# MEMS_Motion_Sensor.net
KiCad netlist of a schematic drawn in Altium Designer
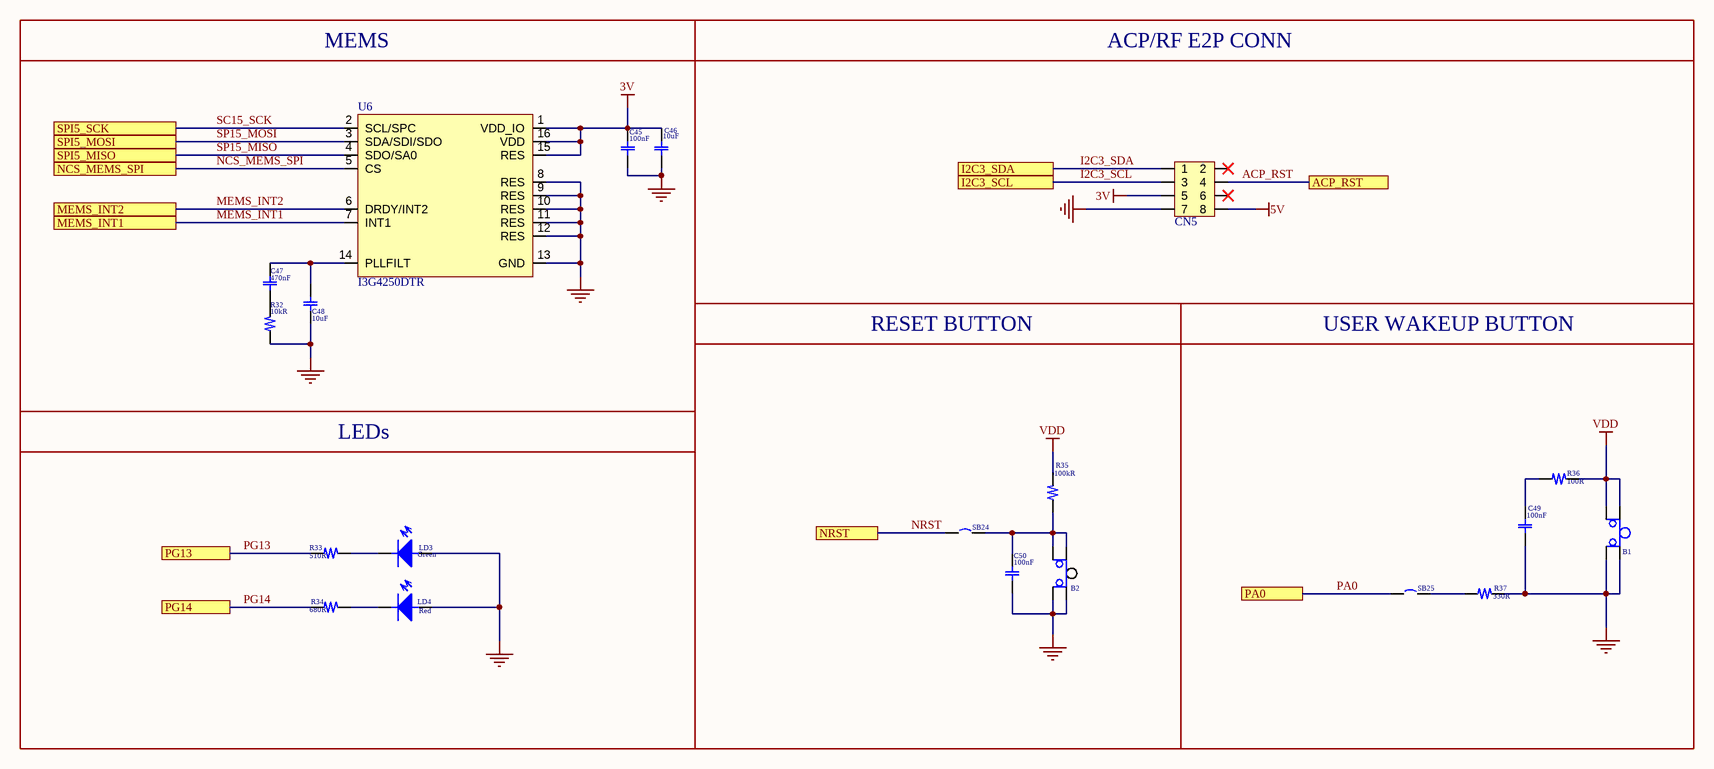
[diagram p0: MEMS Motion Sensor.SchDoc]

(export (version "E")
  (design (tool "Eeschema 10.0.6"))
  (components
    (comp (ref "B1")
      (value "KSC721G LFS")
      (footprint "Blue_Button")
      (description "Switch Tactile N.O. SPST Round Button Gull Wing 0.05A 32VDC 1VA 300000Cycle 1.7N SMD T/R")
      (fields (field (name "MANUFACTURER") "ITT C&K") (field (name "MANUFACTURER PART NUMBER") "KSC721GLFS"))
      (libsource (lib "STM32") (part "BLUE SWITCH TACTILE"))
    )
    (comp (ref "B2")
      (value "KSC321GLFS")
      (footprint "Black_Buttom")
      (fields (field (name "MANUFACTURER") "ITT C&K"))
      (libsource (lib "STM32") (part "BLACK SWITCH TACTILE"))
    )
    (comp (ref "C45")
      (value "100nF")
      (footprint "CAP-0402")
      (description "Multilayer Ceramic Capacitor, 0.1 uF, 25 V, ± 10%, X7R, 0402 [1005 Metric]")
      (fields
        (field (name "MANUFACTURER") "Yageo")
        (field (name "MANUFACTURER PART NUMBER") "CC0402KRX7R7BB104")
      )
      (libsource (lib "STM32") (part "CAP CER 100nF 16V X7R 0402"))
    )
    (comp (ref "C46")
      (value "10uF")
      (footprint "CAP-0603")
      (description "Multilayer Ceramic Capacitor, 10 uF, 10 V, ± 10%, X5R, 0603 [1608 Metric]")
      (fields
        (field (name "MANUFACTURER") "Samsung")
        (field (name "MANUFACTURER PART NUMBER") "CL10A106KP8NNNC")
      )
      (libsource (lib "STM32") (part "CAP CER 10UF 10V X5R 0603"))
    )
    (comp (ref "C47")
      (value "470nF")
      (footprint "CAP-0603")
      (description "Multilayer Ceramic Capacitor, 0.47 uF, 16 V, ± 10%, X7R, 0603 [1608 Metric]")
      (fields
        (field (name "MANUFACTURER") "Yageo")
        (field (name "MANUFACTURER PART NUMBER") "CC0603KRX7R7BB474")
      )
      (libsource (lib "STM32") (part "CAP CER 470nF 16V X7R 0603"))
    )
    (comp (ref "C48")
      (value "10uF")
      (footprint "CAP-0603")
      (description "Multilayer Ceramic Capacitor, 10 uF, 10 V, ± 10%, X5R, 0603 [1608 Metric]")
      (fields
        (field (name "MANUFACTURER") "Samsung")
        (field (name "MANUFACTURER PART NUMBER") "CL10A106KP8NNNC")
      )
      (libsource (lib "STM32") (part "CAP CER 10UF 10V X5R 0603"))
    )
    (comp (ref "C49")
      (value "100nF")
      (footprint "CAP-0402")
      (description "Multilayer Ceramic Capacitor, 0.1 uF, 25 V, ± 10%, X7R, 0402 [1005 Metric]")
      (fields
        (field (name "MANUFACTURER") "Yageo")
        (field (name "MANUFACTURER PART NUMBER") "CC0402KRX7R7BB104")
      )
      (libsource (lib "STM32") (part "CAP CER 100nF 16V X7R 0402"))
    )
    (comp (ref "C50")
      (value "100nF")
      (footprint "CAP-0402")
      (description "Multilayer Ceramic Capacitor, 0.1 uF, 25 V, ± 10%, X7R, 0402 [1005 Metric]")
      (fields
        (field (name "MANUFACTURER") "Yageo")
        (field (name "MANUFACTURER PART NUMBER") "CC0402KRX7R7BB104")
      )
      (libsource (lib "STM32") (part "CAP CER 100nF 16V X7R 0402"))
    )
    (comp (ref "CN5")
      (value "SSM-104-L-DH")
      (footprint "CONN-2*8")
      (description "Connector Socket Strip SKT 8 POS 2.54mm Solder RA SMD")
      (fields (field (name "MANUFACTURER") "Samtec"))
      (libsource (lib "STM32") (part "CONN 2*8POS 2.54MM"))
    )
    (comp (ref "LD3")
      (value "150060VS75000")
      (footprint "LED-GREEN-0603")
      (description "WURTH ELEKTRONIK - 150060VS75000 - LED, Green, SMD, 0603, 30 mA, 2 V, 570 nm")
      (fields (field (name "MANUFACTURER") "Wurth Electronics") (field (name "COLOR") "Green"))
      (libsource (lib "STM32") (part "LED GREEN CLEAR 0603 SMD"))
    )
    (comp (ref "LD4")
      (value "150060RS75000")
      (footprint "LED-RED-0603")
      (description "LED Low-Power Uni-Color Red 630nm 2V 2-Pin Chip 0603(1608Metric) T/R")
      (fields (field (name "MANUFACTURER") "Wurth Electronics") (field (name "COLOR") "Red"))
      (libsource (lib "STM32") (part "LED RED CLEAR 0603 SMD"))
    )
    (comp (ref "R32")
      (value "10kR")
      (footprint "RES-0402")
      (description "SMD Chip Resistor, 10 kOhm, ± 1%, 63 mW, 0402 [1005 Metric], Thick Film, General Purpose")
      (fields
        (field (name "MANUFACTURER") "Yageo")
        (field (name "MANUFACTURER PART NUMBER") "RC0402FR-0710KL")
      )
      (libsource (lib "STM32") (part "RES 10K OHM 1% 1/16W 0402"))
    )
    (comp (ref "R33")
      (value "510R")
      (footprint "RES-0402")
      (description "SMD Chip Resistor, 510 kOhm, ± 1%, 63 mW, 0402 [1005 Metric], Thick Film, General Purpose")
      (fields
        (field (name "MANUFACTURER") "Yageo")
        (field (name "MANUFACTURER PART NUMBER") "RC0402FR-07510KL")
      )
      (libsource (lib "STM32") (part "RES 510K OHM 1% 1/16W 0402"))
    )
    (comp (ref "R34")
      (value "680R")
      (footprint "RES-0603")
      (description "SMD Chip Resistor, 680 Ohm, ± 1%, 100 mW, 0603 [1608 Metric], Thick Film, General Purpose")
      (fields
        (field (name "MANUFACTURER") "Yageo")
        (field (name "MANUFACTURER PART NUMBER") "RC0603FR-07680RL")
      )
      (libsource (lib "STM32") (part "RES 680 OHM 1% 1/10W 0603"))
    )
    (comp (ref "R35")
      (value "100kR")
      (footprint "RES-0402")
      (description "SMD Chip Resistor, 100 kOhm, ± 1%, 63 mW, 0402 [1005 Metric], Thick Film, General Purpose")
      (fields
        (field (name "MANUFACTURER") "Yageo")
        (field (name "MANUFACTURER PART NUMBER") "RC0402FR-07100KL")
      )
      (libsource (lib "STM32") (part "RES 100K OHM 1% 1/16W 0402"))
    )
    (comp (ref "R36")
      (value "100R")
      (footprint "RES-0402")
      (description "SMD Chip Resistor, 100 Ohm, ± 1%, 63 mW, 0402 [1005 Metric], Thick Film, General Purpose")
      (fields
        (field (name "MANUFACTURER") "Yageo")
        (field (name "MANUFACTURER PART NUMBER") "RC0402FR-07100RL")
      )
      (libsource (lib "STM32") (part "RES 100 OHM 1% 1/16W 0402"))
    )
    (comp (ref "R37")
      (value "330R")
      (footprint "RES-0402")
      (description "SMD Chip Resistor, 330 Ohm, ± 1%, 63 mW, 0402 [1005 Metric], Thick Film, General Purpose")
      (fields
        (field (name "MANUFACTURER") "Yageo")
        (field (name "MANUFACTURER PART NUMBER") "RC0402FR-07330RL")
      )
      (libsource (lib "STM32") (part "RES 330 OHM 1% 1/16W 0402"))
    )
    (comp (ref "SB24")
      (value "RC0402JR-070RL")
      (footprint "RES-0402")
      (description "Zero Ohm Resistor, Jumper, 0402 [1005 Metric], Thick Film, 62.5 mW, 1 A, Surface Mount")
      (fields
        (field (name "MANUFACTURER") "Yageo")
        (field (name "MANUFACTURER PART NUMBER") "RC0603JR-070RL")
      )
      (libsource (lib "STM32") (part "RES 0 OHM JUMPER 1/10W 0603"))
    )
    (comp (ref "SB25")
      (value "RC0402JR-070RL")
      (footprint "RES-0402")
      (description "Zero Ohm Resistor, Jumper, 0402 [1005 Metric], Thick Film, 62.5 mW, 1 A, Surface Mount")
      (fields
        (field (name "MANUFACTURER") "Yageo")
        (field (name "MANUFACTURER PART NUMBER") "RC0603JR-070RL")
      )
      (libsource (lib "STM32") (part "RES 0 OHM JUMPER 1/10W 0603"))
    )
    (comp (ref "U6")
      (value "I3G4250DTR")
      (footprint "LGA-16")
      (description "I3G4250D Series 3.6 V 6.1 mA Low-Power 3-Axis Angular Rate Sensor - LGA-16")
      (fields (field (name "MANUFACTURER") "STMicroelectronics"))
      (libsource (lib "STM32") (part "MEMS MOTION SENSOR 3AXIS 16LGA"))
    )
  )
  (nets
    (net (code "1") (name "/ACP_RST") (class "Default")
      (node (ref "CN5") (pin "4") (pinfunction "4_4") (pintype "passive"))
    )
    (net (code "2") (name "/I2C3_SCL") (class "Default")
      (node (ref "CN5") (pin "3") (pinfunction "3_3") (pintype "passive"))
    )
    (net (code "3") (name "/I2C3_SDA") (class "Default")
      (node (ref "CN5") (pin "1") (pinfunction "1_1") (pintype "passive"))
    )
    (net (code "4") (name "/MEMS_INT1") (class "Default")
      (node (ref "U6") (pin "7") (pinfunction "INT1_7") (pintype "passive"))
    )
    (net (code "5") (name "/MEMS_INT2") (class "Default")
      (node (ref "U6") (pin "6") (pinfunction "DRDY/INT2_6") (pintype "passive"))
    )
    (net (code "6") (name "/NCS_MEMS_SPI") (class "Default")
      (node (ref "U6") (pin "5") (pinfunction "CS_5") (pintype "passive"))
    )
    (net (code "7") (name "/NRST") (class "Default")
      (node (ref "SB24") (pin "1") (pinfunction "1_1") (pintype "passive"))
    )
    (net (code "8") (name "/PA0") (class "Default")
      (node (ref "SB25") (pin "1") (pinfunction "1_1") (pintype "passive"))
    )
    (net (code "9") (name "/PG13") (class "Default")
      (node (ref "R33") (pin "1") (pinfunction "1_1") (pintype "passive"))
    )
    (net (code "10") (name "/PG14") (class "Default")
      (node (ref "R34") (pin "1") (pinfunction "1_1") (pintype "passive"))
    )
    (net (code "11") (name "/SC15_SCK") (class "Default")
      (node (ref "U6") (pin "2") (pinfunction "SCL/SPC_2") (pintype "passive"))
    )
    (net (code "12") (name "/SP15_MISO") (class "Default")
      (node (ref "U6") (pin "4") (pinfunction "SDO/SA0_4") (pintype "passive"))
    )
    (net (code "13") (name "/SP15_MOSI") (class "Default")
      (node (ref "U6") (pin "3") (pinfunction "SDA/SDI/SDO_3") (pintype "passive"))
    )
    (net (code "14") (name "3V") (class "Default")
      (node (ref "C45") (pin "2") (pinfunction "2_2") (pintype "passive"))
      (node (ref "C46") (pin "2") (pinfunction "2_2") (pintype "passive"))
      (node (ref "CN5") (pin "5") (pinfunction "5_5") (pintype "passive"))
      (node (ref "U6") (pin "1") (pinfunction "VDD_IO_1") (pintype "passive"))
      (node (ref "U6") (pin "15") (pinfunction "RES_15") (pintype "passive"))
      (node (ref "U6") (pin "16") (pinfunction "VDD_16") (pintype "passive"))
    )
    (net (code "15") (name "5V") (class "Default")
      (node (ref "CN5") (pin "8") (pinfunction "8_8") (pintype "passive"))
    )
    (net (code "16") (name "GND") (class "Default")
      (node (ref "B1") (pin "2") (pinfunction "2_2") (pintype "passive"))
      (node (ref "B1") (pin "3") (pinfunction "3_3") (pintype "passive"))
      (node (ref "B2") (pin "2") (pinfunction "2_2") (pintype "passive"))
      (node (ref "B2") (pin "3") (pinfunction "3_3") (pintype "passive"))
      (node (ref "C45") (pin "1") (pinfunction "1_1") (pintype "passive"))
      (node (ref "C46") (pin "1") (pinfunction "1_1") (pintype "passive"))
      (node (ref "C48") (pin "1") (pinfunction "1_1") (pintype "passive"))
      (node (ref "C49") (pin "1") (pinfunction "1_1") (pintype "passive"))
      (node (ref "C50") (pin "1") (pinfunction "1_1") (pintype "passive"))
      (node (ref "CN5") (pin "7") (pinfunction "7_7") (pintype "passive"))
      (node (ref "LD3") (pin "2") (pinfunction "2_2") (pintype "passive"))
      (node (ref "LD4") (pin "2") (pinfunction "2_2") (pintype "passive"))
      (node (ref "R32") (pin "1") (pinfunction "1_1") (pintype "passive"))
      (node (ref "R37") (pin "2") (pinfunction "2_2") (pintype "passive"))
      (node (ref "U6") (pin "10") (pinfunction "RES_10") (pintype "passive"))
      (node (ref "U6") (pin "11") (pinfunction "RES_11") (pintype "passive"))
      (node (ref "U6") (pin "12") (pinfunction "RES_12") (pintype "passive"))
      (node (ref "U6") (pin "13") (pinfunction "GND_13") (pintype "passive"))
      (node (ref "U6") (pin "8") (pinfunction "RES_8") (pintype "passive"))
      (node (ref "U6") (pin "9") (pinfunction "RES_9") (pintype "passive"))
    )
    (net (code "17") (name "Net-(B2-Pad1)") (class "Default")
      (node (ref "B2") (pin "1") (pinfunction "1_1") (pintype "passive"))
      (node (ref "B2") (pin "4") (pinfunction "4_4") (pintype "passive"))
      (node (ref "C50") (pin "2") (pinfunction "2_2") (pintype "passive"))
      (node (ref "R35") (pin "1") (pinfunction "1_1") (pintype "passive"))
      (node (ref "SB24") (pin "2") (pinfunction "2_2") (pintype "passive"))
    )
    (net (code "18") (name "Net-(C47-Pad1)") (class "Default")
      (node (ref "C47") (pin "1") (pinfunction "1_1") (pintype "passive"))
      (node (ref "R32") (pin "2") (pinfunction "2_2") (pintype "passive"))
    )
    (net (code "19") (name "Net-(C49-Pad2)") (class "Default")
      (node (ref "C49") (pin "2") (pinfunction "2_2") (pintype "passive"))
      (node (ref "R36") (pin "1") (pinfunction "1_1") (pintype "passive"))
    )
    (net (code "20") (name "Net-(LD3-Pad1)") (class "Default")
      (node (ref "LD3") (pin "1") (pinfunction "1_1") (pintype "passive"))
      (node (ref "R33") (pin "2") (pinfunction "2_2") (pintype "passive"))
    )
    (net (code "21") (name "Net-(LD4-Pad1)") (class "Default")
      (node (ref "LD4") (pin "1") (pinfunction "1_1") (pintype "passive"))
      (node (ref "R34") (pin "2") (pinfunction "2_2") (pintype "passive"))
    )
    (net (code "22") (name "Net-(R37-Pad1)") (class "Default")
      (node (ref "R37") (pin "1") (pinfunction "1_1") (pintype "passive"))
      (node (ref "SB25") (pin "2") (pinfunction "2_2") (pintype "passive"))
    )
    (net (code "23") (name "Net-(U6-PLLFILT)") (class "Default")
      (node (ref "C47") (pin "2") (pinfunction "2_2") (pintype "passive"))
      (node (ref "C48") (pin "2") (pinfunction "2_2") (pintype "passive"))
      (node (ref "U6") (pin "14") (pinfunction "PLLFILT_14") (pintype "passive"))
    )
    (net (code "24") (name "VDD") (class "Default")
      (node (ref "B1") (pin "1") (pinfunction "1_1") (pintype "passive"))
      (node (ref "B1") (pin "4") (pinfunction "4_4") (pintype "passive"))
      (node (ref "R35") (pin "2") (pinfunction "2_2") (pintype "passive"))
      (node (ref "R36") (pin "2") (pinfunction "2_2") (pintype "passive"))
    )
    (net (code "25") (name "unconnected-(CN5-Pad2)") (class "Default")
      (node (ref "CN5") (pin "2") (pinfunction "2_2") (pintype "passive+no_connect"))
    )
    (net (code "26") (name "unconnected-(CN5-Pad6)") (class "Default")
      (node (ref "CN5") (pin "6") (pinfunction "6_6") (pintype "passive+no_connect"))
    )
  )
)
